# debounce_hw.net
KiCad netlist of a schematic drawn in EAGLE
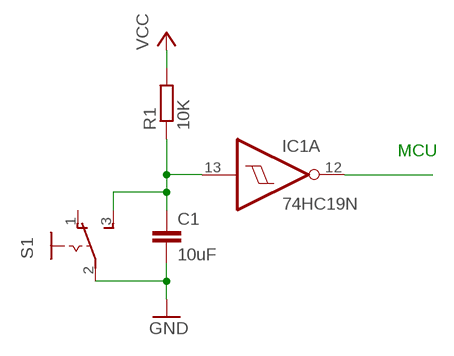
[diagram p0: schematic, sheet 1]

(export (version "E")
  (design (tool "Eeschema 10.0.6"))
  (components
    (comp (ref "C1")
      (value "10uF")
      (footprint "eagle-import:C050-035X075")
      (libsource (lib "eagle-import") (part "C-EU050-035X075"))
    )
    (comp (ref "IC1")
      (value "74HC19N")
      (footprint "eagle-import:DIL14")
      (libsource (lib "eagle-import") (part "7419NHC"))
    )
    (comp (ref "R1")
      (value "10K")
      (footprint "eagle-import:0411_15")
      (libsource (lib "eagle-import") (part "R-EU_0411/15"))
    )
    (comp (ref "S1")
      (value "M251")
      (footprint "eagle-import:M251")
      (libsource (lib "eagle-import") (part "M251"))
    )
  )
  (nets
    (net (code "1") (name "GND") (class "Default")
      (node (ref "C1") (pin "2") (pinfunction "2_2") (pintype "passive"))
      (node (ref "S1") (pin "2") (pinfunction "P_2") (pintype "passive"))
    )
    (net (code "2") (name "Net-(IC1A-I)") (class "Default")
      (node (ref "C1") (pin "1") (pinfunction "1_1") (pintype "passive"))
      (node (ref "IC1") (pin "13") (pinfunction "I_13") (pintype "input"))
      (node (ref "R1") (pin "1") (pinfunction "1_1") (pintype "passive"))
      (node (ref "S1") (pin "3") (pinfunction "S_3") (pintype "passive"))
    )
    (net (code "3") (name "VCC") (class "Default")
      (node (ref "R1") (pin "2") (pinfunction "2_2") (pintype "passive"))
    )
    (net (code "4") (name "unconnected-(IC1A-O-Pad12)") (class "Default")
      (node (ref "IC1") (pin "12") (pinfunction "O_12") (pintype "output"))
    )
    (net (code "5") (name "unconnected-(S1-O-Pad1)") (class "Default")
      (node (ref "S1") (pin "1") (pinfunction "O_1") (pintype "passive"))
    )
  )
)
